# ActiveFilters.net
KiCad netlist of a schematic drawn in Altium Designer
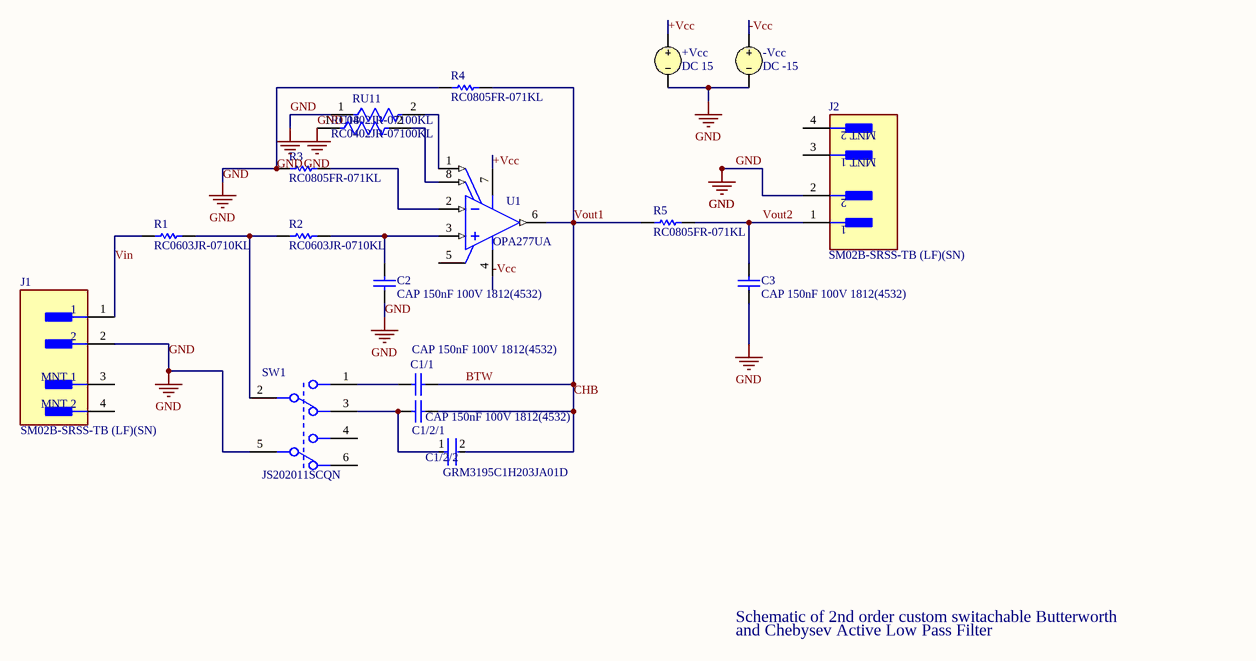
[diagram p0: ActiveFilters.SchDoc]

(export (version "E")
  (design (tool "Eeschema 10.0.6"))
  (components
    (comp (ref "+Vcc")
      (value "DC 15")
      (description "Voltage Source")
      (fields (field (name "PUBLISHER") "Altium Limited"))
      (libsource (lib "Simulation Generic Components") (part "VSRC"))
    )
    (comp (ref "-Vcc")
      (value "DC -15")
      (description "Voltage Source")
      (fields (field (name "PUBLISHER") "Altium Limited"))
      (libsource (lib "Simulation Generic Components") (part "VSRC"))
    )
    (comp (ref "C1/1")
      (value "CAP 150nF 100V 1812(4532)")
      (footprint "CAPC1812(4532)230_N")
      (description "CAP 150nF 100V ±5% 1812 (4532 Metric) Thickness 2.3mm SMD")
      (fields (field (name "TOLERANCE") "Â±5%"))
      (libsource (lib "Altium Content Vault") (part "CAP"))
    )
    (comp (ref "C1/2/1")
      (value "CAP 150nF 100V 1812(4532)")
      (footprint "CAPC1812(4532)230_N")
      (description "CAP 150nF 100V ±5% 1812 (4532 Metric) Thickness 2.3mm SMD")
      (fields (field (name "TOLERANCE") "Â±5%"))
      (libsource (lib "Altium Content Vault") (part "CAP"))
    )
    (comp (ref "C1/2/2")
      (value "GRM3195C1H203JA01D")
      (footprint "FP-GRM319-0_15-IPC_C")
      (description "Chip Multilayer Ceramic Capacitors for General Purpose, 1206, 20000pF, C0G, 30ppm/°C, 5%, 50V")
      (fields (field (name "VOLTAGE") "50V") (field (name "TOLERANCE") "5%"))
      (libsource (lib "Altium Content Vault") (part "b4654b650e69147ec39a6b967a45e02"))
    )
    (comp (ref "C2")
      (value "CAP 150nF 100V 1812(4532)")
      (footprint "CAPC1812(4532)230_N")
      (description "CAP 150nF 100V ±5% 1812 (4532 Metric) Thickness 2.3mm SMD")
      (fields (field (name "TOLERANCE") "Â±5%"))
      (libsource (lib "Altium Content Vault") (part "CAP"))
    )
    (comp (ref "C3")
      (value "CAP 150nF 100V 1812(4532)")
      (footprint "CAPC1812(4532)230_N")
      (description "CAP 150nF 100V ±5% 1812 (4532 Metric) Thickness 2.3mm SMD")
      (fields (field (name "TOLERANCE") "Â±5%"))
      (libsource (lib "Altium Content Vault") (part "CAP"))
    )
    (comp (ref "J1")
      (value "SM02B-SRSS-TB (LF)(SN)")
      (footprint "FP-SM02B-SRSS-TB_LF_SN-MFG")
      (description "CONN HEADER SMD R/A 2POS 1MM")
      (libsource (lib "Altium Content Vault") (part "029478cb6d4f2fad0cd2a245525ee6d"))
    )
    (comp (ref "J2")
      (value "SM02B-SRSS-TB (LF)(SN)")
      (footprint "FP-SM02B-SRSS-TB_LF_SN-MFG")
      (description "CONN HEADER SMD R/A 2POS 1MM")
      (libsource (lib "") (part "029478cb6d4f2fad0cd2a245525ee6d_1"))
    )
    (comp (ref "R1")
      (value "RC0603JR-0710KL")
      (footprint "RESC1608X55X25ML10T15")
      (description "Resistor, 10 KOhm, +/- 5%, 100 mW, -55 to 155 degC, 0603 (1608 Metric), RoHS, Tape and Reel")
      (fields (field (name "MANUFACTURER") "Yageo") (field (name "TOLERANCE") "5%"))
      (libsource (lib "Altium Content Vault") (part "RES-2"))
    )
    (comp (ref "R2")
      (value "RC0603JR-0710KL")
      (footprint "RESC1608X55X25ML10T15")
      (description "Resistor, 10 KOhm, +/- 5%, 100 mW, -55 to 155 degC, 0603 (1608 Metric), RoHS, Tape and Reel")
      (fields (field (name "MANUFACTURER") "Yageo") (field (name "TOLERANCE") "5%"))
      (libsource (lib "Altium Content Vault") (part "RES-2"))
    )
    (comp (ref "R3")
      (value "RC0805FR-071KL")
      (footprint "RESC2013X60X35ML10T20")
      (description "Chip Resistor, 1 KOhm, +/- 1%, 125 mW, -55 to 155 degC, 0805 (2012 Metric), RoHS, Tape and Reel")
      (fields (field (name "TOLERANCE") "1%") (field (name "MANUFACTURER") "Yageo"))
      (libsource (lib "Altium Content Vault") (part "RES-2"))
    )
    (comp (ref "R4")
      (value "RC0805FR-071KL")
      (footprint "RESC2013X60X35ML10T20")
      (description "Chip Resistor, 1 KOhm, +/- 1%, 125 mW, -55 to 155 degC, 0805 (2012 Metric), RoHS, Tape and Reel")
      (fields (field (name "TOLERANCE") "1%") (field (name "MANUFACTURER") "Yageo"))
      (libsource (lib "Altium Content Vault") (part "RES-2"))
    )
    (comp (ref "R5")
      (value "RC0805FR-071KL")
      (footprint "RESC2013X60X35ML10T20")
      (description "Chip Resistor, 1 KOhm, +/- 1%, 125 mW, -55 to 155 degC, 0805 (2012 Metric), RoHS, Tape and Reel")
      (fields (field (name "TOLERANCE") "1%") (field (name "MANUFACTURER") "Yageo"))
      (libsource (lib "Altium Content Vault") (part "RES-2"))
    )
    (comp (ref "RU11")
      (value "RC0402JR-07100KL")
      (footprint "FP-RC0402-0_4-IPC_A")
      (description "RES 100K OHM 5% 1/16W 0402")
      (fields (field (name "TOLERANCE") "5%"))
      (libsource (lib "Altium Content Vault") (part "1029c3af85768c4190bb7ad29bc67b5"))
    )
    (comp (ref "RU18")
      (value "RC0402JR-07100KL")
      (footprint "FP-RC0402-0_4-IPC_A")
      (description "RES 100K OHM 5% 1/16W 0402")
      (fields (field (name "TOLERANCE") "5%"))
      (libsource (lib "Altium Content Vault") (part "1029c3af85768c4190bb7ad29bc67b5"))
    )
    (comp (ref "SW1")
      (value "JS202011SCQN")
      (footprint "FP-JS202011SCQN-MFG")
      (description "SWITCH SLIDE DPDT 300MA 6V")
      (libsource (lib "Altium Content Vault") (part "ac99ea1af431c19115f5225061c5c88"))
    )
    (comp (ref "U1")
      (value "OPA277UA")
      (footprint "D0008A_N")
      (fields (field (name "MANUFACTURER") "Texas Instruments"))
      (libsource (lib "Altium Content Vault") (part "TI-OPA277_132-8"))
    )
  )
  (nets
    (net (code "1") (name "/+Vcc") (class "Default")
      (node (ref "+Vcc") (pin "1") (pinfunction "1_1") (pintype "passive"))
      (node (ref "U1") (pin "7") (pinfunction "V+_7") (pintype "power_in"))
    )
    (net (code "2") (name "/-Vcc") (class "Default")
      (node (ref "-Vcc") (pin "1") (pinfunction "1_1") (pintype "passive"))
      (node (ref "U1") (pin "4") (pinfunction "V-_4") (pintype "power_in"))
    )
    (net (code "3") (name "/BTW") (class "Default")
      (node (ref "C1/1") (pin "1") (pinfunction "1_1") (pintype "passive"))
      (node (ref "C1/2/1") (pin "1") (pinfunction "1_1") (pintype "passive"))
      (node (ref "C1/2/2") (pin "2") (pinfunction "2_2") (pintype "passive"))
      (node (ref "R4") (pin "2") (pinfunction "2_2") (pintype "passive"))
      (node (ref "R5") (pin "1") (pinfunction "1_1") (pintype "passive"))
      (node (ref "U1") (pin "6") (pinfunction "OUT_6") (pintype "output"))
    )
    (net (code "4") (name "/Vin") (class "Default")
      (node (ref "J1") (pin "1") (pinfunction "1_1") (pintype "passive"))
      (node (ref "R1") (pin "1") (pinfunction "1_1") (pintype "passive"))
    )
    (net (code "5") (name "/Vout2") (class "Default")
      (node (ref "C3") (pin "2") (pinfunction "2_2") (pintype "passive"))
      (node (ref "J2") (pin "1") (pinfunction "1_1") (pintype "passive"))
      (node (ref "R5") (pin "2") (pinfunction "2_2") (pintype "passive"))
    )
    (net (code "6") (name "GND") (class "Default")
      (node (ref "+Vcc") (pin "2") (pinfunction "2_2") (pintype "passive"))
      (node (ref "-Vcc") (pin "2") (pinfunction "2_2") (pintype "passive"))
      (node (ref "C2") (pin "1") (pinfunction "1_1") (pintype "passive"))
      (node (ref "C3") (pin "1") (pinfunction "1_1") (pintype "passive"))
      (node (ref "J1") (pin "2") (pinfunction "2_2") (pintype "passive"))
      (node (ref "J2") (pin "2") (pinfunction "2_2") (pintype "passive"))
      (node (ref "R3") (pin "1") (pinfunction "1_1") (pintype "passive"))
      (node (ref "R4") (pin "1") (pinfunction "1_1") (pintype "passive"))
      (node (ref "RU11") (pin "1") (pinfunction "1_1") (pintype "passive"))
      (node (ref "RU18") (pin "1") (pinfunction "1_1") (pintype "passive"))
      (node (ref "SW1") (pin "5") (pinfunction "5_5") (pintype "passive"))
    )
    (net (code "7") (name "Net-(C1/1-Pad2)") (class "Default")
      (node (ref "C1/1") (pin "2") (pinfunction "2_2") (pintype "passive"))
      (node (ref "SW1") (pin "1") (pinfunction "1_1") (pintype "passive"))
    )
    (net (code "8") (name "Net-(C1/2/1-Pad2)") (class "Default")
      (node (ref "C1/2/1") (pin "2") (pinfunction "2_2") (pintype "passive"))
      (node (ref "C1/2/2") (pin "1") (pinfunction "1_1") (pintype "passive"))
      (node (ref "SW1") (pin "3") (pinfunction "3_3") (pintype "passive"))
    )
    (net (code "9") (name "Net-(R1-Pad2)") (class "Default")
      (node (ref "R1") (pin "2") (pinfunction "2_2") (pintype "passive"))
      (node (ref "R2") (pin "1") (pinfunction "1_1") (pintype "passive"))
      (node (ref "SW1") (pin "2") (pinfunction "2_2") (pintype "passive"))
    )
    (net (code "10") (name "Net-(RU11-Pad2)") (class "Default")
      (node (ref "RU11") (pin "2") (pinfunction "2_2") (pintype "passive"))
      (node (ref "U1") (pin "1") (pinfunction "OFFSET_TRIM_1") (pintype "input"))
    )
    (net (code "11") (name "Net-(RU18-Pad2)") (class "Default")
      (node (ref "RU18") (pin "2") (pinfunction "2_2") (pintype "passive"))
      (node (ref "U1") (pin "8") (pinfunction "OFFSET_TRIM_8") (pintype "input"))
    )
    (net (code "12") (name "Net-(U1-IN+)") (class "Default")
      (node (ref "C2") (pin "2") (pinfunction "2_2") (pintype "passive"))
      (node (ref "R2") (pin "2") (pinfunction "2_2") (pintype "passive"))
      (node (ref "U1") (pin "3") (pinfunction "IN+_3") (pintype "input"))
    )
    (net (code "13") (name "Net-(U1-IN-)") (class "Default")
      (node (ref "R3") (pin "2") (pinfunction "2_2") (pintype "passive"))
      (node (ref "U1") (pin "2") (pinfunction "IN-_2") (pintype "input"))
    )
    (net (code "14") (name "unconnected-(J1-MNT_1-Pad3)") (class "Default")
      (node (ref "J1") (pin "3") (pinfunction "MNT_1_3") (pintype "passive"))
    )
    (net (code "15") (name "unconnected-(J1-MNT_2-Pad4)") (class "Default")
      (node (ref "J1") (pin "4") (pinfunction "MNT_2_4") (pintype "passive"))
    )
    (net (code "16") (name "unconnected-(J2-MNT_1-Pad3)") (class "Default")
      (node (ref "J2") (pin "3") (pinfunction "MNT_1_3") (pintype "passive"))
    )
    (net (code "17") (name "unconnected-(J2-MNT_2-Pad4)") (class "Default")
      (node (ref "J2") (pin "4") (pinfunction "MNT_2_4") (pintype "passive"))
    )
    (net (code "18") (name "unconnected-(SW1-Pad4)") (class "Default")
      (node (ref "SW1") (pin "4") (pinfunction "4_4") (pintype "passive"))
    )
    (net (code "19") (name "unconnected-(SW1-Pad6)") (class "Default")
      (node (ref "SW1") (pin "6") (pinfunction "6_6") (pintype "passive"))
    )
    (net (code "20") (name "unconnected-(U1-NC-Pad5)") (class "Default")
      (node (ref "U1") (pin "5") (pinfunction "NC_5") (pintype "passive"))
    )
  )
)
